# JoystickConnector_v3.net
KiCad netlist of a schematic drawn in EAGLE
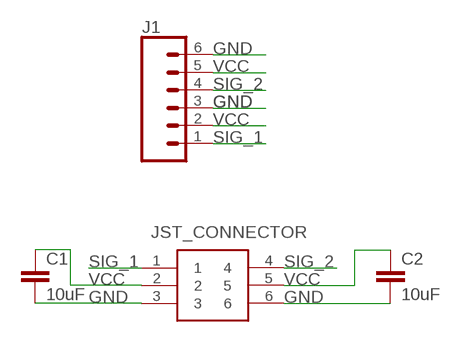
[diagram p0: schematic, sheet 1]

(export (version "E")
  (design (tool "Eeschema 10.0.6"))
  (components
    (comp (ref "C1")
      (value "10uF")
      (footprint "eagle-import:0805")
      (libsource (lib "eagle-import") (part "10UF-0805-10V-10%"))
    )
    (comp (ref "C2")
      (value "10uF")
      (footprint "eagle-import:0805")
      (libsource (lib "eagle-import") (part "10UF-0805-10V-10%"))
    )
    (comp (ref "J1")
      (value "CONN_06SILK_FEMALE_PTH")
      (footprint "eagle-import:1X06")
      (libsource (lib "eagle-import") (part "CONN_06SILK_FEMALE_PTH"))
    )
    (comp (ref "JST_CONNECTOR")
      (value "0532610671")
      (footprint "eagle-import:0532610671")
      (libsource (lib "eagle-import") (part "0532610671"))
    )
  )
  (nets
    (net (code "1") (name "/GND") (class "Default")
      (node (ref "C1") (pin "2") (pinfunction "2_2") (pintype "passive"))
      (node (ref "C2") (pin "2") (pinfunction "2_2") (pintype "passive"))
      (node (ref "J1") (pin "3") (pinfunction "3_3") (pintype "passive"))
      (node (ref "J1") (pin "6") (pinfunction "6_6") (pintype "passive"))
      (node (ref "JST_CONNECTOR") (pin "3") (pinfunction "3_3") (pintype "bidirectional"))
      (node (ref "JST_CONNECTOR") (pin "6") (pinfunction "6_6") (pintype "bidirectional"))
    )
    (net (code "2") (name "/SIG_1") (class "Default")
      (node (ref "J1") (pin "1") (pinfunction "1_1") (pintype "passive"))
      (node (ref "JST_CONNECTOR") (pin "1") (pinfunction "1_1") (pintype "bidirectional"))
    )
    (net (code "3") (name "/SIG_2") (class "Default")
      (node (ref "J1") (pin "4") (pinfunction "4_4") (pintype "passive"))
      (node (ref "JST_CONNECTOR") (pin "4") (pinfunction "4_4") (pintype "bidirectional"))
    )
    (net (code "4") (name "/VCC") (class "Default")
      (node (ref "C1") (pin "1") (pinfunction "1_1") (pintype "passive"))
      (node (ref "C2") (pin "1") (pinfunction "1_1") (pintype "passive"))
      (node (ref "J1") (pin "2") (pinfunction "2_2") (pintype "passive"))
      (node (ref "J1") (pin "5") (pinfunction "5_5") (pintype "passive"))
      (node (ref "JST_CONNECTOR") (pin "2") (pinfunction "2_2") (pintype "bidirectional"))
      (node (ref "JST_CONNECTOR") (pin "5") (pinfunction "5_5") (pintype "bidirectional"))
    )
  )
)
